# IFAT6_QFP.net
KiCad netlist of a schematic drawn in Altium Designer
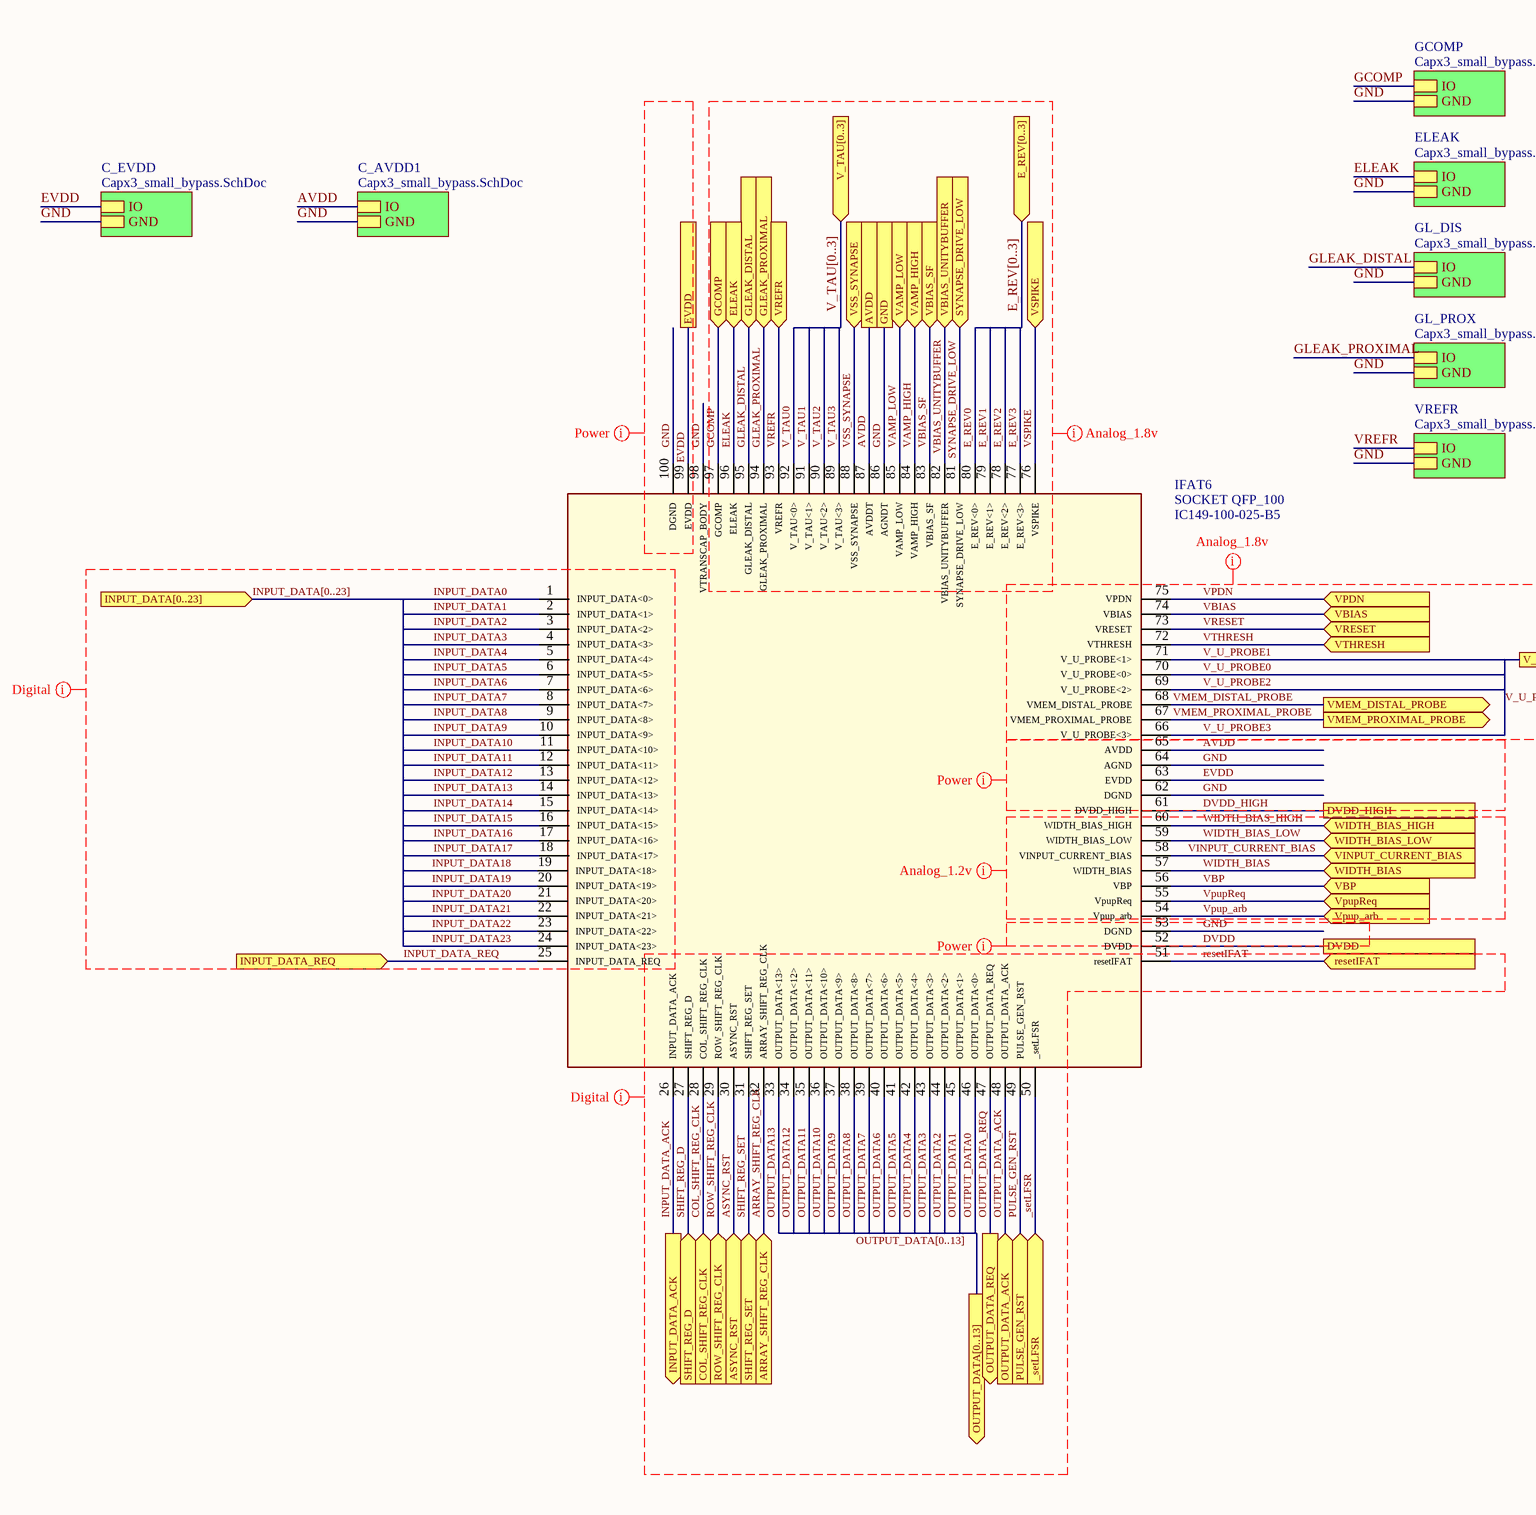
[diagram p0: IFAT6_QFP.SchDoc, left]
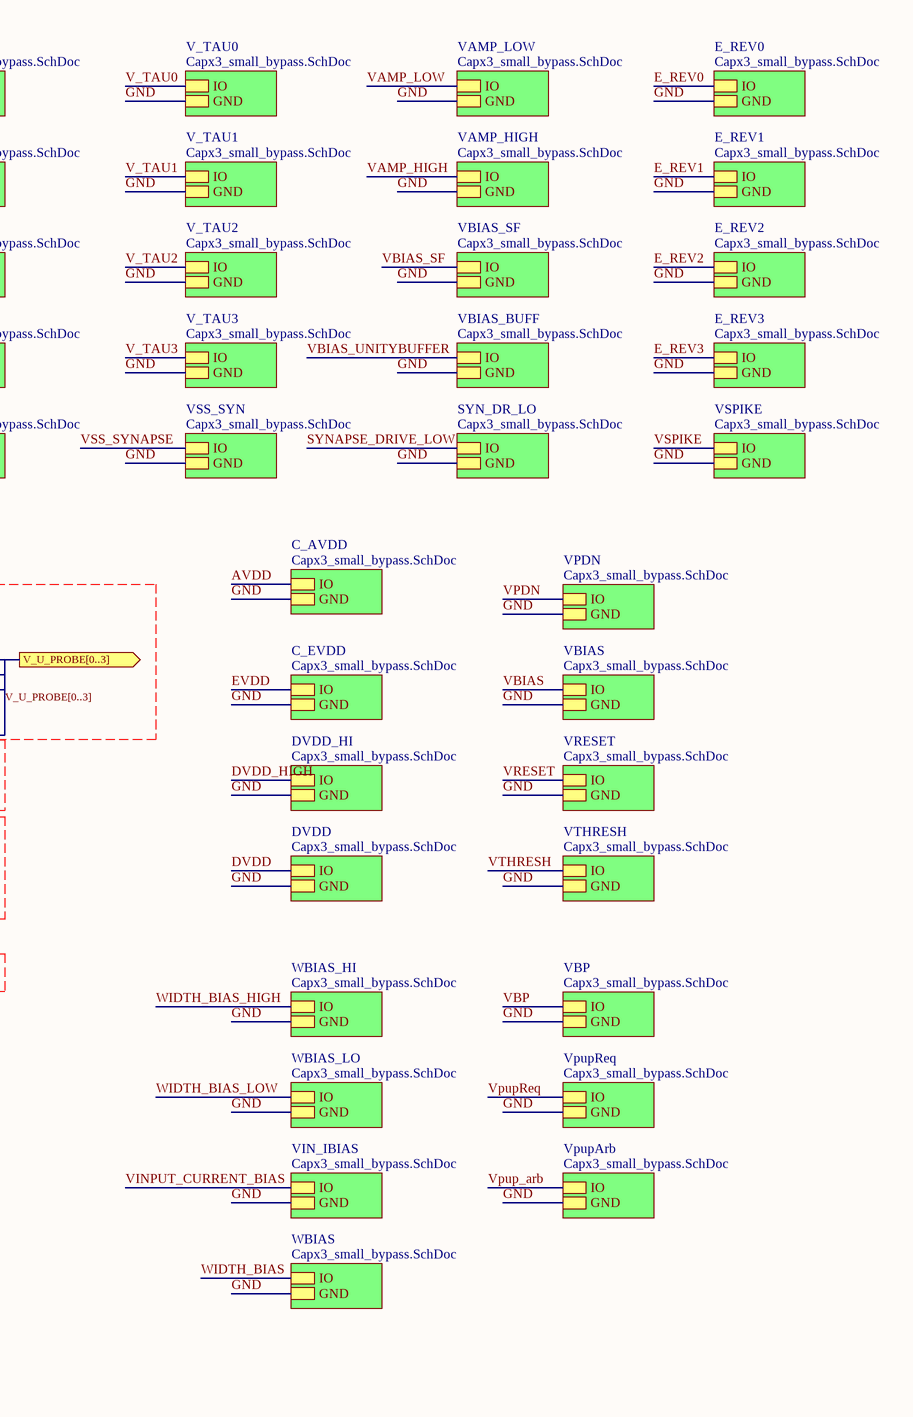
[diagram p1: IFAT6_QFP.SchDoc, right]

(export (version "E")
  (design (tool "Eeschema 10.0.6"))
  (components
    (comp (ref "IFAT6")
      (value "SOCKET QFP_100")
      (footprint "YAMAICHI_IC149-100-025-B5")
      (description "100 pin QFP")
      (fields
        (field (name "MOUSER PART NUMBER") "945-IC149-100-025-B5")
        (field (name "MANUFACTURER_PART_NUMBER") "IC149-100-025-B5")
      )
      (libsource (lib "IFAT6") (part "SOCKET QFP_100"))
    )
  )
  (nets
    (net (code "1") (name "/ARRAY_SHIFT_REG_CLK") (class "Default")
      (node (ref "IFAT6") (pin "32") (pinfunction "ARRAY_SHIFT_REG_CLK_32") (pintype "passive"))
    )
    (net (code "2") (name "/ASYNC_RST") (class "Default")
      (node (ref "IFAT6") (pin "30") (pinfunction "ASYNC_RST_30") (pintype "passive"))
    )
    (net (code "3") (name "/AVDD") (class "Default")
      (node (ref "IFAT6") (pin "65") (pinfunction "AVDD_65") (pintype "passive"))
      (node (ref "IFAT6") (pin "87") (pinfunction "AVDDT_87") (pintype "passive"))
    )
    (net (code "4") (name "/COL_SHIFT_REG_CLK") (class "Default")
      (node (ref "IFAT6") (pin "28") (pinfunction "COL_SHIFT_REG_CLK_28") (pintype "passive"))
    )
    (net (code "5") (name "/DVDD") (class "Default")
      (node (ref "IFAT6") (pin "52") (pinfunction "DVDD_52") (pintype "passive"))
    )
    (net (code "6") (name "/DVDD_HIGH") (class "Default")
      (node (ref "IFAT6") (pin "61") (pinfunction "DVDD_HIGH_61") (pintype "passive"))
    )
    (net (code "7") (name "/ELEAK") (class "Default")
      (node (ref "IFAT6") (pin "96") (pinfunction "ELEAK_96") (pintype "passive"))
    )
    (net (code "8") (name "/EVDD") (class "Default")
      (node (ref "IFAT6") (pin "63") (pinfunction "EVDD_63") (pintype "passive"))
      (node (ref "IFAT6") (pin "99") (pinfunction "EVDD_99") (pintype "passive"))
    )
    (net (code "9") (name "/E_REV0") (class "Default")
      (node (ref "IFAT6") (pin "80") (pinfunction "E_REV<0>_80") (pintype "passive"))
    )
    (net (code "10") (name "/E_REV1") (class "Default")
      (node (ref "IFAT6") (pin "79") (pinfunction "E_REV<1>_79") (pintype "passive"))
    )
    (net (code "11") (name "/E_REV2") (class "Default")
      (node (ref "IFAT6") (pin "78") (pinfunction "E_REV<2>_78") (pintype "passive"))
    )
    (net (code "12") (name "/E_REV3") (class "Default")
      (node (ref "IFAT6") (pin "77") (pinfunction "E_REV<3>_77") (pintype "passive"))
    )
    (net (code "14") (name "/GCOMP") (class "Default")
      (node (ref "IFAT6") (pin "97") (pinfunction "GCOMP_97") (pintype "passive"))
    )
    (net (code "15") (name "/GLEAK_DISTAL") (class "Default")
      (node (ref "IFAT6") (pin "95") (pinfunction "GLEAK_DISTAL_95") (pintype "passive"))
    )
    (net (code "16") (name "/GLEAK_PROXIMAL") (class "Default")
      (node (ref "IFAT6") (pin "94") (pinfunction "GLEAK_PROXIMAL_94") (pintype "passive"))
    )
    (net (code "17") (name "/GND") (class "Default")
      (node (ref "IFAT6") (pin "100") (pinfunction "DGND_100") (pintype "passive"))
      (node (ref "IFAT6") (pin "53") (pinfunction "DGND_53") (pintype "passive"))
      (node (ref "IFAT6") (pin "62") (pinfunction "DGND_62") (pintype "passive"))
      (node (ref "IFAT6") (pin "64") (pinfunction "AGND_64") (pintype "passive"))
      (node (ref "IFAT6") (pin "86") (pinfunction "AGNDT_86") (pintype "passive"))
      (node (ref "IFAT6") (pin "98") (pinfunction "VTRANSCAP_BODY_98") (pintype "passive"))
    )
    (net (code "18") (name "/INPUT_DATA0") (class "Default")
      (node (ref "IFAT6") (pin "1") (pinfunction "INPUT_DATA<0>_1") (pintype "passive"))
    )
    (net (code "19") (name "/INPUT_DATA1") (class "Default")
      (node (ref "IFAT6") (pin "2") (pinfunction "INPUT_DATA<1>_2") (pintype "passive"))
    )
    (net (code "20") (name "/INPUT_DATA2") (class "Default")
      (node (ref "IFAT6") (pin "3") (pinfunction "INPUT_DATA<2>_3") (pintype "passive"))
    )
    (net (code "21") (name "/INPUT_DATA3") (class "Default")
      (node (ref "IFAT6") (pin "4") (pinfunction "INPUT_DATA<3>_4") (pintype "passive"))
    )
    (net (code "22") (name "/INPUT_DATA4") (class "Default")
      (node (ref "IFAT6") (pin "5") (pinfunction "INPUT_DATA<4>_5") (pintype "passive"))
    )
    (net (code "23") (name "/INPUT_DATA5") (class "Default")
      (node (ref "IFAT6") (pin "6") (pinfunction "INPUT_DATA<5>_6") (pintype "passive"))
    )
    (net (code "24") (name "/INPUT_DATA6") (class "Default")
      (node (ref "IFAT6") (pin "7") (pinfunction "INPUT_DATA<6>_7") (pintype "passive"))
    )
    (net (code "25") (name "/INPUT_DATA7") (class "Default")
      (node (ref "IFAT6") (pin "8") (pinfunction "INPUT_DATA<7>_8") (pintype "passive"))
    )
    (net (code "26") (name "/INPUT_DATA8") (class "Default")
      (node (ref "IFAT6") (pin "9") (pinfunction "INPUT_DATA<8>_9") (pintype "passive"))
    )
    (net (code "27") (name "/INPUT_DATA9") (class "Default")
      (node (ref "IFAT6") (pin "10") (pinfunction "INPUT_DATA<9>_10") (pintype "passive"))
    )
    (net (code "28") (name "/INPUT_DATA10") (class "Default")
      (node (ref "IFAT6") (pin "11") (pinfunction "INPUT_DATA<10>_11") (pintype "passive"))
    )
    (net (code "29") (name "/INPUT_DATA11") (class "Default")
      (node (ref "IFAT6") (pin "12") (pinfunction "INPUT_DATA<11>_12") (pintype "passive"))
    )
    (net (code "30") (name "/INPUT_DATA12") (class "Default")
      (node (ref "IFAT6") (pin "13") (pinfunction "INPUT_DATA<12>_13") (pintype "passive"))
    )
    (net (code "31") (name "/INPUT_DATA13") (class "Default")
      (node (ref "IFAT6") (pin "14") (pinfunction "INPUT_DATA<13>_14") (pintype "passive"))
    )
    (net (code "32") (name "/INPUT_DATA14") (class "Default")
      (node (ref "IFAT6") (pin "15") (pinfunction "INPUT_DATA<14>_15") (pintype "passive"))
    )
    (net (code "33") (name "/INPUT_DATA15") (class "Default")
      (node (ref "IFAT6") (pin "16") (pinfunction "INPUT_DATA<15>_16") (pintype "passive"))
    )
    (net (code "34") (name "/INPUT_DATA16") (class "Default")
      (node (ref "IFAT6") (pin "17") (pinfunction "INPUT_DATA<16>_17") (pintype "passive"))
    )
    (net (code "35") (name "/INPUT_DATA17") (class "Default")
      (node (ref "IFAT6") (pin "18") (pinfunction "INPUT_DATA<17>_18") (pintype "passive"))
    )
    (net (code "36") (name "/INPUT_DATA18") (class "Default")
      (node (ref "IFAT6") (pin "19") (pinfunction "INPUT_DATA<18>_19") (pintype "passive"))
    )
    (net (code "37") (name "/INPUT_DATA19") (class "Default")
      (node (ref "IFAT6") (pin "20") (pinfunction "INPUT_DATA<19>_20") (pintype "passive"))
    )
    (net (code "38") (name "/INPUT_DATA20") (class "Default")
      (node (ref "IFAT6") (pin "21") (pinfunction "INPUT_DATA<20>_21") (pintype "passive"))
    )
    (net (code "39") (name "/INPUT_DATA21") (class "Default")
      (node (ref "IFAT6") (pin "22") (pinfunction "INPUT_DATA<21>_22") (pintype "passive"))
    )
    (net (code "40") (name "/INPUT_DATA22") (class "Default")
      (node (ref "IFAT6") (pin "23") (pinfunction "INPUT_DATA<22>_23") (pintype "passive"))
    )
    (net (code "41") (name "/INPUT_DATA23") (class "Default")
      (node (ref "IFAT6") (pin "24") (pinfunction "INPUT_DATA<23>_24") (pintype "passive"))
    )
    (net (code "43") (name "/INPUT_DATA_ACK") (class "Default")
      (node (ref "IFAT6") (pin "26") (pinfunction "INPUT_DATA_ACK_26") (pintype "passive"))
    )
    (net (code "44") (name "/INPUT_DATA_REQ") (class "Default")
      (node (ref "IFAT6") (pin "25") (pinfunction "INPUT_DATA_REQ_25") (pintype "passive"))
    )
    (net (code "45") (name "/OUTPUT_DATA0") (class "Default")
      (node (ref "IFAT6") (pin "46") (pinfunction "OUTPUT_DATA<0>_46") (pintype "passive"))
    )
    (net (code "46") (name "/OUTPUT_DATA1") (class "Default")
      (node (ref "IFAT6") (pin "45") (pinfunction "OUTPUT_DATA<1>_45") (pintype "passive"))
    )
    (net (code "47") (name "/OUTPUT_DATA2") (class "Default")
      (node (ref "IFAT6") (pin "44") (pinfunction "OUTPUT_DATA<2>_44") (pintype "passive"))
    )
    (net (code "48") (name "/OUTPUT_DATA3") (class "Default")
      (node (ref "IFAT6") (pin "43") (pinfunction "OUTPUT_DATA<3>_43") (pintype "passive"))
    )
    (net (code "49") (name "/OUTPUT_DATA4") (class "Default")
      (node (ref "IFAT6") (pin "42") (pinfunction "OUTPUT_DATA<4>_42") (pintype "passive"))
    )
    (net (code "50") (name "/OUTPUT_DATA5") (class "Default")
      (node (ref "IFAT6") (pin "41") (pinfunction "OUTPUT_DATA<5>_41") (pintype "passive"))
    )
    (net (code "51") (name "/OUTPUT_DATA6") (class "Default")
      (node (ref "IFAT6") (pin "40") (pinfunction "OUTPUT_DATA<6>_40") (pintype "passive"))
    )
    (net (code "52") (name "/OUTPUT_DATA7") (class "Default")
      (node (ref "IFAT6") (pin "39") (pinfunction "OUTPUT_DATA<7>_39") (pintype "passive"))
    )
    (net (code "53") (name "/OUTPUT_DATA8") (class "Default")
      (node (ref "IFAT6") (pin "38") (pinfunction "OUTPUT_DATA<8>_38") (pintype "passive"))
    )
    (net (code "54") (name "/OUTPUT_DATA9") (class "Default")
      (node (ref "IFAT6") (pin "37") (pinfunction "OUTPUT_DATA<9>_37") (pintype "passive"))
    )
    (net (code "55") (name "/OUTPUT_DATA10") (class "Default")
      (node (ref "IFAT6") (pin "36") (pinfunction "OUTPUT_DATA<10>_36") (pintype "passive"))
    )
    (net (code "56") (name "/OUTPUT_DATA11") (class "Default")
      (node (ref "IFAT6") (pin "35") (pinfunction "OUTPUT_DATA<11>_35") (pintype "passive"))
    )
    (net (code "57") (name "/OUTPUT_DATA12") (class "Default")
      (node (ref "IFAT6") (pin "34") (pinfunction "OUTPUT_DATA<12>_34") (pintype "passive"))
    )
    (net (code "58") (name "/OUTPUT_DATA13") (class "Default")
      (node (ref "IFAT6") (pin "33") (pinfunction "OUTPUT_DATA<13>_33") (pintype "passive"))
    )
    (net (code "60") (name "/OUTPUT_DATA_ACK") (class "Default")
      (node (ref "IFAT6") (pin "48") (pinfunction "OUTPUT_DATA_ACK_48") (pintype "passive"))
    )
    (net (code "61") (name "/OUTPUT_DATA_REQ") (class "Default")
      (node (ref "IFAT6") (pin "47") (pinfunction "OUTPUT_DATA_REQ_47") (pintype "passive"))
    )
    (net (code "62") (name "/PULSE_GEN_RST") (class "Default")
      (node (ref "IFAT6") (pin "49") (pinfunction "PULSE_GEN_RST_49") (pintype "passive"))
    )
    (net (code "63") (name "/ROW_SHIFT_REG_CLK") (class "Default")
      (node (ref "IFAT6") (pin "29") (pinfunction "ROW_SHIFT_REG_CLK_29") (pintype "passive"))
    )
    (net (code "64") (name "/SHIFT_REG_D") (class "Default")
      (node (ref "IFAT6") (pin "27") (pinfunction "SHIFT_REG_D_27") (pintype "passive"))
    )
    (net (code "65") (name "/SHIFT_REG_SET") (class "Default")
      (node (ref "IFAT6") (pin "31") (pinfunction "SHIFT_REG_SET_31") (pintype "passive"))
    )
    (net (code "66") (name "/SYNAPSE_DRIVE_LOW") (class "Default")
      (node (ref "IFAT6") (pin "81") (pinfunction "SYNAPSE_DRIVE_LOW_81") (pintype "passive"))
    )
    (net (code "67") (name "/VAMP_HIGH") (class "Default")
      (node (ref "IFAT6") (pin "84") (pinfunction "VAMP_HIGH_84") (pintype "passive"))
    )
    (net (code "68") (name "/VAMP_LOW") (class "Default")
      (node (ref "IFAT6") (pin "85") (pinfunction "VAMP_LOW_85") (pintype "passive"))
    )
    (net (code "69") (name "/VBIAS") (class "Default")
      (node (ref "IFAT6") (pin "74") (pinfunction "VBIAS_74") (pintype "passive"))
    )
    (net (code "70") (name "/VBIAS_SF") (class "Default")
      (node (ref "IFAT6") (pin "83") (pinfunction "VBIAS_SF_83") (pintype "passive"))
    )
    (net (code "71") (name "/VBIAS_UNITYBUFFER") (class "Default")
      (node (ref "IFAT6") (pin "82") (pinfunction "VBIAS_UNITYBUFFER_82") (pintype "passive"))
    )
    (net (code "72") (name "/VBP") (class "Default")
      (node (ref "IFAT6") (pin "56") (pinfunction "VBP_56") (pintype "passive"))
    )
    (net (code "73") (name "/VINPUT_CURRENT_BIAS") (class "Default")
      (node (ref "IFAT6") (pin "58") (pinfunction "VINPUT_CURRENT_BIAS_58") (pintype "passive"))
    )
    (net (code "74") (name "/VMEM_DISTAL_PROBE") (class "Default")
      (node (ref "IFAT6") (pin "68") (pinfunction "VMEM_DISTAL_PROBE_68") (pintype "passive"))
    )
    (net (code "75") (name "/VMEM_PROXIMAL_PROBE") (class "Default")
      (node (ref "IFAT6") (pin "67") (pinfunction "VMEM_PROXIMAL_PROBE_67") (pintype "passive"))
    )
    (net (code "76") (name "/VPDN") (class "Default")
      (node (ref "IFAT6") (pin "75") (pinfunction "VPDN_75") (pintype "passive"))
    )
    (net (code "77") (name "/VREFR") (class "Default")
      (node (ref "IFAT6") (pin "93") (pinfunction "VREFR_93") (pintype "passive"))
    )
    (net (code "78") (name "/VRESET") (class "Default")
      (node (ref "IFAT6") (pin "73") (pinfunction "VRESET_73") (pintype "passive"))
    )
    (net (code "79") (name "/VSPIKE") (class "Default")
      (node (ref "IFAT6") (pin "76") (pinfunction "VSPIKE_76") (pintype "passive"))
    )
    (net (code "80") (name "/VSS_SYNAPSE") (class "Default")
      (node (ref "IFAT6") (pin "88") (pinfunction "VSS_SYNAPSE_88") (pintype "passive"))
    )
    (net (code "81") (name "/VTHRESH") (class "Default")
      (node (ref "IFAT6") (pin "72") (pinfunction "VTHRESH_72") (pintype "passive"))
    )
    (net (code "82") (name "/V_TAU0") (class "Default")
      (node (ref "IFAT6") (pin "92") (pinfunction "V_TAU<0>_92") (pintype "passive"))
    )
    (net (code "83") (name "/V_TAU1") (class "Default")
      (node (ref "IFAT6") (pin "91") (pinfunction "V_TAU<1>_91") (pintype "passive"))
    )
    (net (code "84") (name "/V_TAU2") (class "Default")
      (node (ref "IFAT6") (pin "90") (pinfunction "V_TAU<2>_90") (pintype "passive"))
    )
    (net (code "85") (name "/V_TAU3") (class "Default")
      (node (ref "IFAT6") (pin "89") (pinfunction "V_TAU<3>_89") (pintype "passive"))
    )
    (net (code "87") (name "/V_U_PROBE0") (class "Default")
      (node (ref "IFAT6") (pin "70") (pinfunction "V_U_PROBE<0>_70") (pintype "passive"))
    )
    (net (code "88") (name "/V_U_PROBE1") (class "Default")
      (node (ref "IFAT6") (pin "71") (pinfunction "V_U_PROBE<1>_71") (pintype "passive"))
    )
    (net (code "89") (name "/V_U_PROBE2") (class "Default")
      (node (ref "IFAT6") (pin "69") (pinfunction "V_U_PROBE<2>_69") (pintype "passive"))
    )
    (net (code "90") (name "/V_U_PROBE3") (class "Default")
      (node (ref "IFAT6") (pin "66") (pinfunction "V_U_PROBE<3>_66") (pintype "passive"))
    )
    (net (code "92") (name "/VpupReq") (class "Default")
      (node (ref "IFAT6") (pin "55") (pinfunction "VpupReq_55") (pintype "passive"))
    )
    (net (code "93") (name "/Vpup_arb") (class "Default")
      (node (ref "IFAT6") (pin "54") (pinfunction "Vpup_arb_54") (pintype "passive"))
    )
    (net (code "94") (name "/WIDTH_BIAS") (class "Default")
      (node (ref "IFAT6") (pin "57") (pinfunction "WIDTH_BIAS_57") (pintype "passive"))
    )
    (net (code "95") (name "/WIDTH_BIAS_HIGH") (class "Default")
      (node (ref "IFAT6") (pin "60") (pinfunction "WIDTH_BIAS_HIGH_60") (pintype "passive"))
    )
    (net (code "96") (name "/WIDTH_BIAS_LOW") (class "Default")
      (node (ref "IFAT6") (pin "59") (pinfunction "WIDTH_BIAS_LOW_59") (pintype "passive"))
    )
    (net (code "97") (name "/_setLFSR") (class "Default")
      (node (ref "IFAT6") (pin "50") (pinfunction "_setLFSR_50") (pintype "passive"))
    )
    (net (code "98") (name "/resetIFAT") (class "Default")
      (node (ref "IFAT6") (pin "51") (pinfunction "resetIFAT_51") (pintype "passive"))
    )
  )
)
